# 2015-08-14_11-21-541.net
KiCad netlist of a schematic drawn in Altium Designer
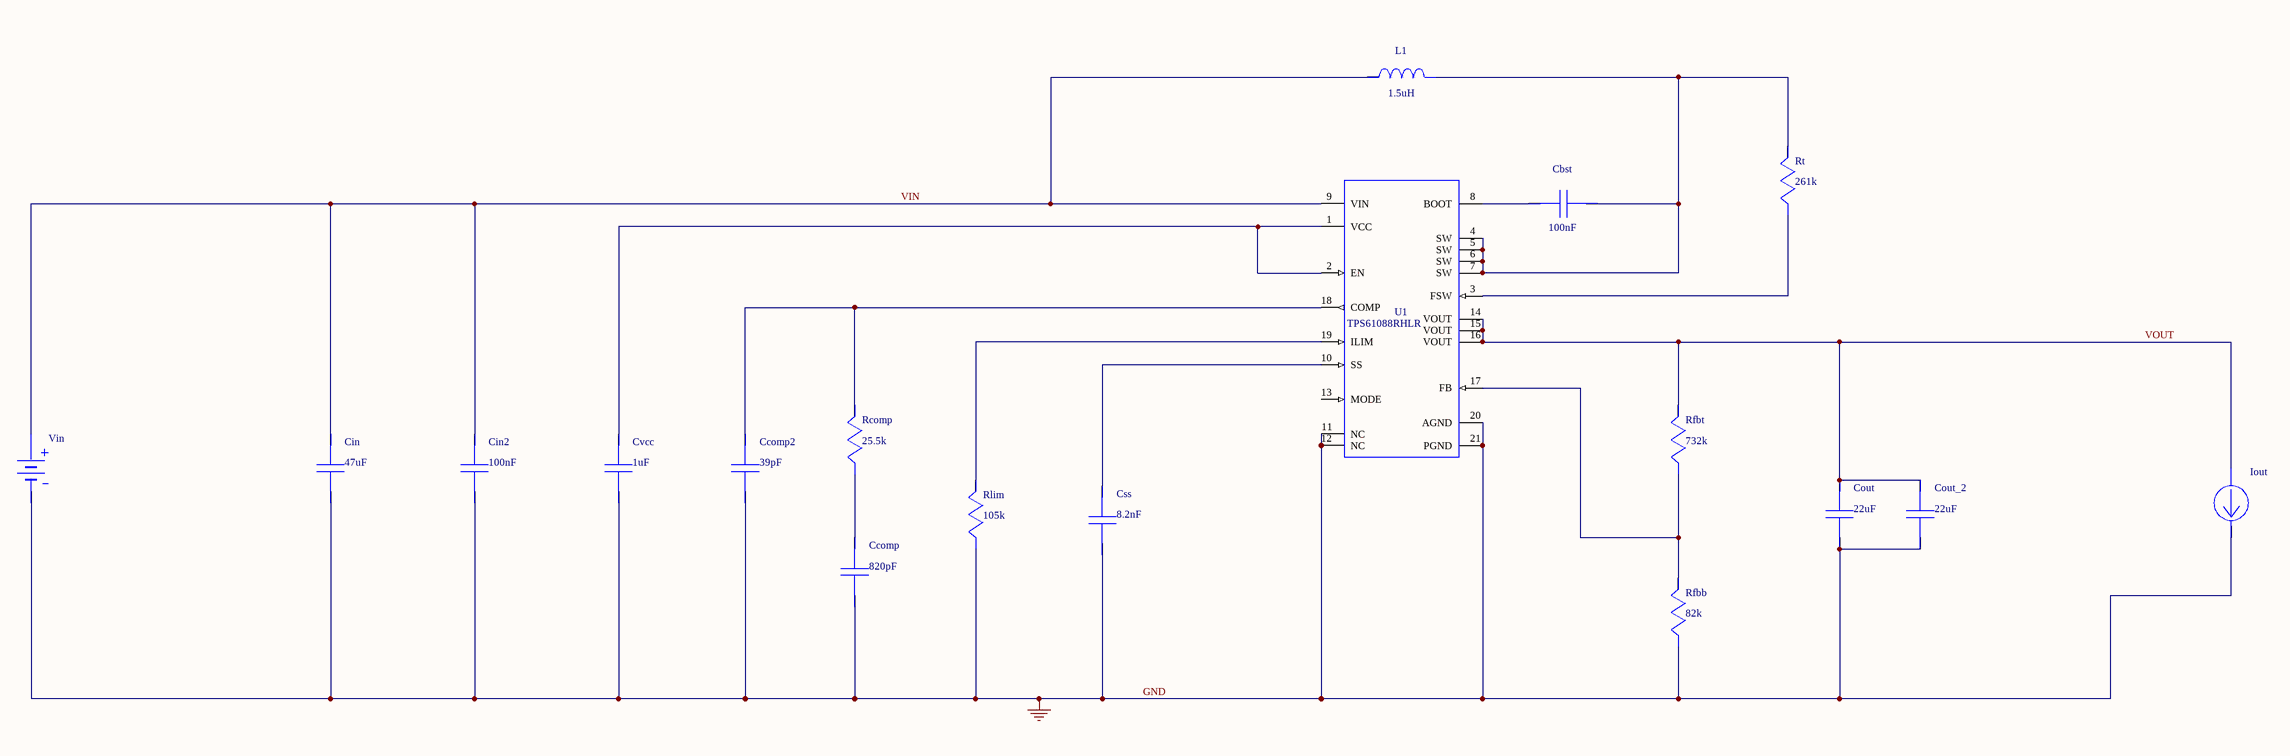
[diagram p0: 2015-08-14_11-21-541.schdoc]

(export (version "E")
  (design (tool "Eeschema 10.0.6"))
  (components
    (comp (ref "Cbst")
      (value "100nF")
      (description "C1005X5R1A104K")
      (libsource (lib "TI WEBENCH") (part "Cbst"))
    )
    (comp (ref "Ccomp")
      (value "820pF")
      (description "CC0805KRX7R9BB82")
      (fields (field (name "MANUFACTURER PART NUMBER") "CC0805KRX7R9BB821"))
      (libsource (lib "TI WEBENCH") (part "Ccomp"))
    )
    (comp (ref "Ccomp2")
      (value "39pF")
      (description "CC0805JRNPO9BN39")
      (fields (field (name "MANUFACTURER PART NUMBER") "CC0805JRNPO9BN390"))
      (libsource (lib "TI WEBENCH") (part "Ccomp2"))
    )
    (comp (ref "Cin")
      (value "47uF")
      (description "GRM32ER61C476ME1")
      (fields (field (name "MANUFACTURER PART NUMBER") "GRM32ER61C476ME15L"))
      (libsource (lib "TI WEBENCH") (part "Cin"))
    )
    (comp (ref "Cin2")
      (value "100nF")
      (description "GRM155R61C104KA8")
      (fields (field (name "MANUFACTURER PART NUMBER") "GRM155R61C104KA88D"))
      (libsource (lib "TI WEBENCH") (part "Cin2"))
    )
    (comp (ref "Cout")
      (value "22uF")
      (description "GRM32ER61E226KE1")
      (fields (field (name "MANUFACTURER PART NUMBER") "GRM32ER61E226KE15L"))
      (libsource (lib "TI WEBENCH") (part "Cout"))
    )
    (comp (ref "Cout_2")
      (value "22uF")
      (description "GRM32ER61E226KE1")
      (fields (field (name "MANUFACTURER PART NUMBER") "GRM32ER61E226KE15L"))
      (libsource (lib "TI WEBENCH") (part "Cout_2"))
    )
    (comp (ref "Css")
      (value "8.2nF")
      (description "GRM155R71C822KA0")
      (fields (field (name "MANUFACTURER PART NUMBER") "GRM155R71C822KA01D"))
      (libsource (lib "TI WEBENCH") (part "Css"))
    )
    (comp (ref "Cvcc")
      (value "1uF")
      (description "C1608X5R1A105K")
      (libsource (lib "TI WEBENCH") (part "Cvcc"))
    )
    (comp (ref "Iout") (value "WB_CURRENT_LOAD") (libsource (lib "TI WEBENCH") (part "Iout")))
    (comp (ref "L1")
      (value "1.5uH")
      (description "Unknown")
      (fields (field (name "MANUFACTURER PART NUMBER") "SRP6540-1R5M"))
      (libsource (lib "TI WEBENCH") (part "L1"))
    )
    (comp (ref "Rcomp")
      (value "25.5k")
      (description "CRCW040225K5FKED")
      (libsource (lib "TI WEBENCH") (part "Rcomp"))
    )
    (comp (ref "Rfbb")
      (value "82k")
      (description "RR1220P-823-D")
      (libsource (lib "TI WEBENCH") (part "Rfbb"))
    )
    (comp (ref "Rfbt")
      (value "732k")
      (description "CRCW0402732KFKED")
      (libsource (lib "TI WEBENCH") (part "Rfbt"))
    )
    (comp (ref "Rlim")
      (value "105k")
      (description "ERJ-8ENF1053V")
      (libsource (lib "TI WEBENCH") (part "Rlim"))
    )
    (comp (ref "Rt") (value "261k") (description "ERJ-8ENF2613V") (libsource (lib "TI WEBENCH") (part "Rt")))
    (comp (ref "U1")
      (value "TPS61088RHLR")
      (fields (field (name "PACKAGEREFERENCE") "TPS61088RHLR"))
      (libsource (lib "TI WEBENCH") (part "U1"))
    )
    (comp (ref "Vin") (value "WB_BATTERY") (libsource (lib "TI WEBENCH") (part "Vin")))
  )
  (nets
    (net (code "1") (name "/VIN") (class "Default")
      (node (ref "Cin") (pin "1") (pinfunction "1_1") (pintype "passive"))
      (node (ref "Cin2") (pin "1") (pinfunction "1_1") (pintype "passive"))
      (node (ref "L1") (pin "1") (pinfunction "1_1") (pintype "passive"))
      (node (ref "U1") (pin "9") (pinfunction "VIN_9") (pintype "power_in"))
      (node (ref "Vin") (pin "1") (pinfunction "+_1") (pintype "passive"))
    )
    (net (code "2") (name "/VOUT") (class "Default")
      (node (ref "Cout") (pin "1") (pinfunction "1_1") (pintype "passive"))
      (node (ref "Cout_2") (pin "1") (pinfunction "1_1") (pintype "passive"))
      (node (ref "Iout") (pin "1") (pinfunction "+_1") (pintype "passive"))
      (node (ref "Rfbt") (pin "1") (pinfunction "1_1") (pintype "passive"))
      (node (ref "U1") (pin "14") (pinfunction "VOUT_14") (pintype "power_in"))
      (node (ref "U1") (pin "15") (pinfunction "VOUT_15") (pintype "power_in"))
      (node (ref "U1") (pin "16") (pinfunction "VOUT_16") (pintype "power_in"))
    )
    (net (code "3") (name "0") (class "Default")
      (node (ref "Ccomp") (pin "2") (pinfunction "2_2") (pintype "passive"))
      (node (ref "Ccomp2") (pin "2") (pinfunction "2_2") (pintype "passive"))
      (node (ref "Cin") (pin "2") (pinfunction "2_2") (pintype "passive"))
      (node (ref "Cin2") (pin "2") (pinfunction "2_2") (pintype "passive"))
      (node (ref "Cout") (pin "2") (pinfunction "2_2") (pintype "passive"))
      (node (ref "Cout_2") (pin "2") (pinfunction "2_2") (pintype "passive"))
      (node (ref "Css") (pin "2") (pinfunction "2_2") (pintype "passive"))
      (node (ref "Cvcc") (pin "2") (pinfunction "2_2") (pintype "passive"))
      (node (ref "Iout") (pin "2") (pinfunction "-_2") (pintype "passive"))
      (node (ref "Rfbb") (pin "2") (pinfunction "2_2") (pintype "passive"))
      (node (ref "Rlim") (pin "2") (pinfunction "2_2") (pintype "passive"))
      (node (ref "U1") (pin "11") (pinfunction "NC_11") (pintype "passive"))
      (node (ref "U1") (pin "12") (pinfunction "NC_12") (pintype "passive"))
      (node (ref "U1") (pin "20") (pinfunction "AGND_20") (pintype "power_in"))
      (node (ref "U1") (pin "21") (pinfunction "PGND_21") (pintype "power_in"))
      (node (ref "Vin") (pin "2") (pinfunction "-_2") (pintype "passive"))
    )
    (net (code "4") (name "Net-(Cbst-Pad2)") (class "Default")
      (node (ref "Cbst") (pin "2") (pinfunction "2_2") (pintype "passive"))
      (node (ref "L1") (pin "2") (pinfunction "2_2") (pintype "passive"))
      (node (ref "Rt") (pin "1") (pinfunction "1_1") (pintype "passive"))
      (node (ref "U1") (pin "4") (pinfunction "SW_4") (pintype "power_in"))
      (node (ref "U1") (pin "5") (pinfunction "SW_5") (pintype "power_in"))
      (node (ref "U1") (pin "6") (pinfunction "SW_6") (pintype "power_in"))
      (node (ref "U1") (pin "7") (pinfunction "SW_7") (pintype "power_in"))
    )
    (net (code "5") (name "Net-(Ccomp-Pad1)") (class "Default")
      (node (ref "Ccomp") (pin "1") (pinfunction "1_1") (pintype "passive"))
      (node (ref "Rcomp") (pin "2") (pinfunction "2_2") (pintype "passive"))
    )
    (net (code "6") (name "Net-(U1-BOOT)") (class "Default")
      (node (ref "Cbst") (pin "1") (pinfunction "1_1") (pintype "passive"))
      (node (ref "U1") (pin "8") (pinfunction "BOOT_8") (pintype "power_in"))
    )
    (net (code "7") (name "Net-(U1-COMP)") (class "Default")
      (node (ref "Ccomp2") (pin "1") (pinfunction "1_1") (pintype "passive"))
      (node (ref "Rcomp") (pin "1") (pinfunction "1_1") (pintype "passive"))
      (node (ref "U1") (pin "18") (pinfunction "COMP_18") (pintype "output"))
    )
    (net (code "8") (name "Net-(U1-EN)") (class "Default")
      (node (ref "Cvcc") (pin "1") (pinfunction "1_1") (pintype "passive"))
      (node (ref "U1") (pin "1") (pinfunction "VCC_1") (pintype "power_in"))
      (node (ref "U1") (pin "2") (pinfunction "EN_2") (pintype "input"))
    )
    (net (code "9") (name "Net-(U1-FB)") (class "Default")
      (node (ref "Rfbb") (pin "1") (pinfunction "1_1") (pintype "passive"))
      (node (ref "Rfbt") (pin "2") (pinfunction "2_2") (pintype "passive"))
      (node (ref "U1") (pin "17") (pinfunction "FB_17") (pintype "input"))
    )
    (net (code "10") (name "Net-(U1-FSW)") (class "Default")
      (node (ref "Rt") (pin "2") (pinfunction "2_2") (pintype "passive"))
      (node (ref "U1") (pin "3") (pinfunction "FSW_3") (pintype "input"))
    )
    (net (code "11") (name "Net-(U1-ILIM)") (class "Default")
      (node (ref "Rlim") (pin "1") (pinfunction "1_1") (pintype "passive"))
      (node (ref "U1") (pin "19") (pinfunction "ILIM_19") (pintype "input"))
    )
    (net (code "12") (name "Net-(U1-SS)") (class "Default")
      (node (ref "Css") (pin "1") (pinfunction "1_1") (pintype "passive"))
      (node (ref "U1") (pin "10") (pinfunction "SS_10") (pintype "input"))
    )
    (net (code "13") (name "unconnected-(U1-MODE-Pad13)") (class "Default")
      (node (ref "U1") (pin "13") (pinfunction "MODE_13") (pintype "input"))
    )
  )
)
